# mpc56_cpuio2.net
KiCad netlist of a schematic drawn in Altium Designer
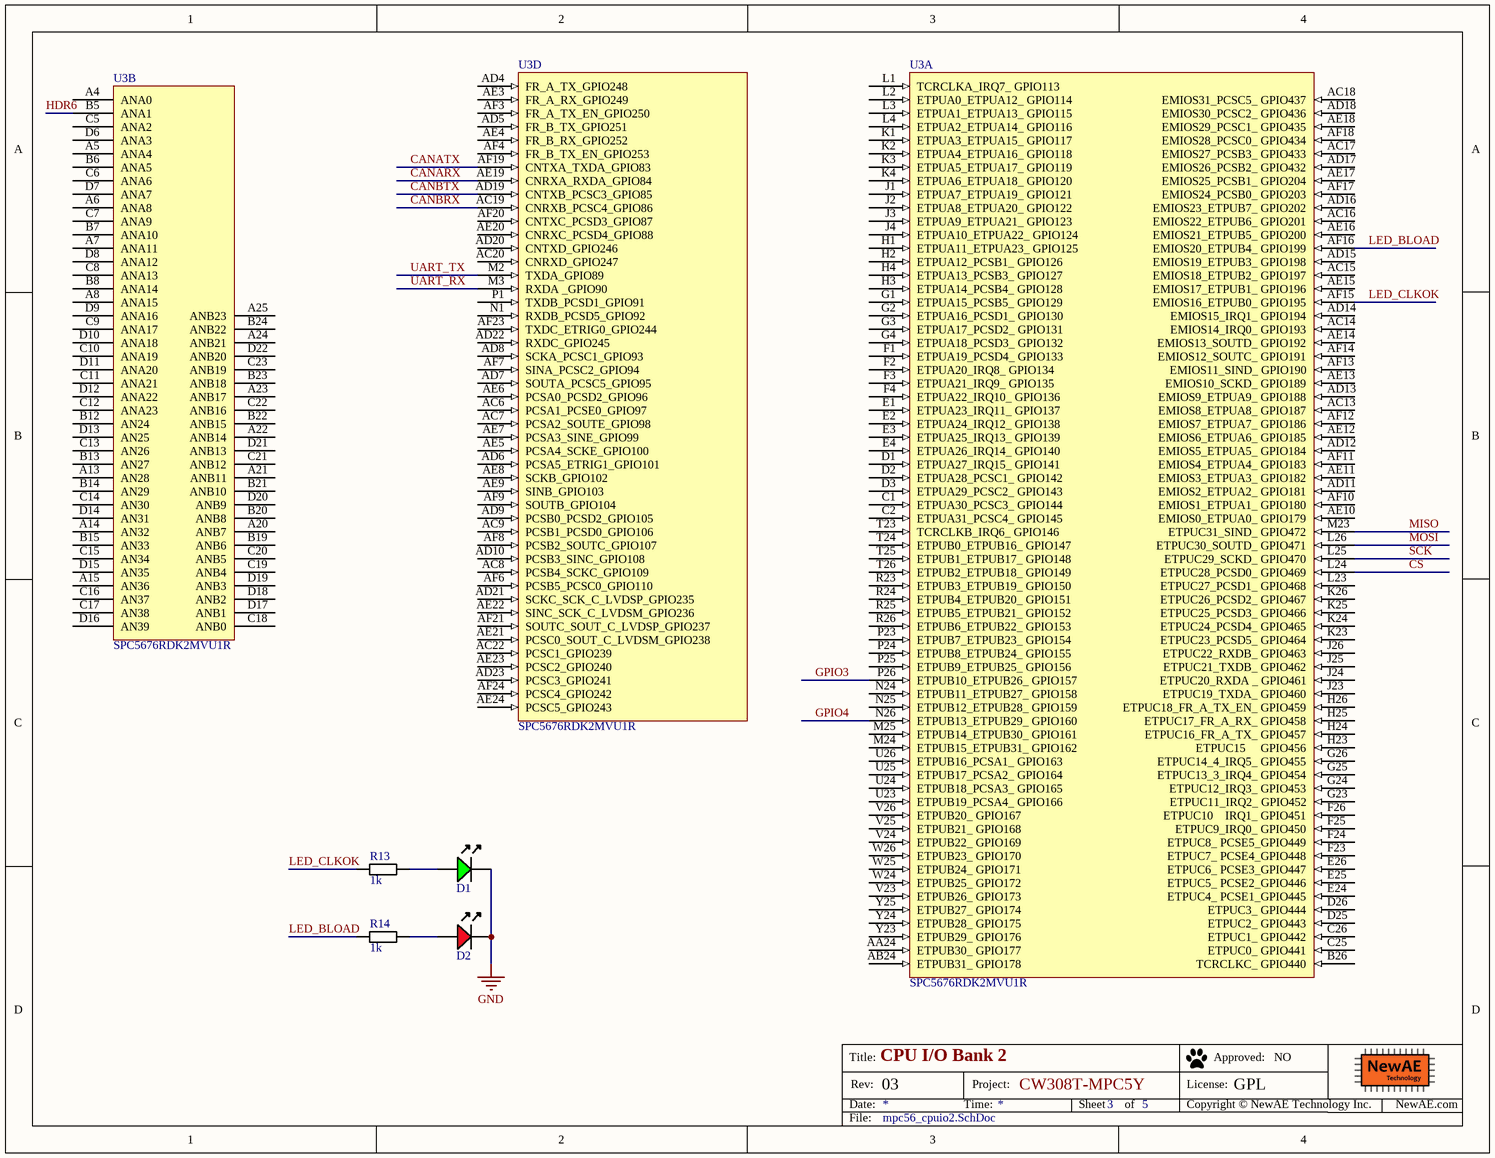
[diagram p0: mpc56_cpuio2.SchDoc]

(export (version "E")
  (design (tool "Eeschema 10.0.6"))
  (components
    (comp (ref "D1")
      (value "LED, 0603, Green")
      (footprint "LED-0603-GREEN")
      (description "Chip LED, Green")
      (fields (field (name "PART NUMBER") "LEDCHIP_0603_GREEN"))
      (libsource (lib "NewAE_AltiumLib") (part "LED_GREEN"))
    )
    (comp (ref "D2")
      (value "LED, 0603, Red")
      (footprint "LED-0603-RED")
      (description "Chip LED, Red")
      (fields (field (name "PART NUMBER") "LEDCHIP_0603_RED"))
      (libsource (lib "NewAE_AltiumLib") (part "LED_RED"))
    )
    (comp (ref "R13")
      (value "1k")
      (footprint "RESC1608X55N")
      (description "1k res, 0603, 1%, 1/10W")
      (fields (field (name "PART NUMBER") "RCHIP-1K-0603") (field (name "TOLERANCE") "1%"))
      (libsource (lib "NewAE_AltiumLib") (part "RES-EU"))
    )
    (comp (ref "R14")
      (value "1k")
      (footprint "RESC1608X55N")
      (description "1k res, 0603, 1%, 1/10W")
      (fields (field (name "PART NUMBER") "RCHIP-1K-0603") (field (name "TOLERANCE") "1%"))
      (libsource (lib "NewAE_AltiumLib") (part "RES-EU"))
    )
    (comp (ref "U3")
      (value "SPC5676RDK2MVU1R")
      (footprint "TEPBGA416_27x27")
      (description "Dual-Core PPC, Automotive")
      (libsource (lib "NewAE_AltiumLib") (part "SPC5676RDK2MVU1R"))
    )
  )
  (nets
    (net (code "1") (name "/CANARX") (class "Default")
      (node (ref "U3") (pin "AE19") (pinfunction "CNRXA_RXDA_GPIO84_AE19") (pintype "input"))
    )
    (net (code "2") (name "/CANATX") (class "Default")
      (node (ref "U3") (pin "AF19") (pinfunction "CNTXA_TXDA_GPIO83_AF19") (pintype "input"))
    )
    (net (code "3") (name "/CANBRX") (class "Default")
      (node (ref "U3") (pin "AC19") (pinfunction "CNRXB_PCSC4_GPIO86_AC19") (pintype "input"))
    )
    (net (code "4") (name "/CANBTX") (class "Default")
      (node (ref "U3") (pin "AD19") (pinfunction "CNTXB_PCSC3_GPIO85_AD19") (pintype "input"))
    )
    (net (code "5") (name "/CS") (class "Default")
      (node (ref "U3") (pin "L24") (pinfunction "ETPUC28_PCSD0__GPIO469_L24") (pintype "input"))
    )
    (net (code "6") (name "/GPIO3") (class "Default")
      (node (ref "U3") (pin "P26") (pinfunction "ETPUB10_ETPUB26__GPIO157_P26") (pintype "input"))
    )
    (net (code "7") (name "/GPIO4") (class "Default")
      (node (ref "U3") (pin "N26") (pinfunction "ETPUB13_ETPUB29__GPIO160_N26") (pintype "input"))
    )
    (net (code "8") (name "/HDR6") (class "Default")
      (node (ref "U3") (pin "B5") (pinfunction "ANA1_B5") (pintype "passive"))
    )
    (net (code "9") (name "/LED_BLOAD") (class "Default")
      (node (ref "R14") (pin "1") (pinfunction "1_1") (pintype "passive"))
      (node (ref "U3") (pin "AF16") (pinfunction "EMIOS20_ETPUB4__GPIO199_AF16") (pintype "input"))
    )
    (net (code "10") (name "/LED_CLKOK") (class "Default")
      (node (ref "R13") (pin "1") (pinfunction "1_1") (pintype "passive"))
      (node (ref "U3") (pin "AF15") (pinfunction "EMIOS16_ETPUB0__GPIO195_AF15") (pintype "input"))
    )
    (net (code "11") (name "/MISO") (class "Default")
      (node (ref "U3") (pin "M23") (pinfunction "ETPUC31_SIND__GPIO472_M23") (pintype "input"))
    )
    (net (code "12") (name "/MOSI") (class "Default")
      (node (ref "U3") (pin "L26") (pinfunction "ETPUC30_SOUTD__GPIO471_L26") (pintype "input"))
    )
    (net (code "13") (name "/SCK") (class "Default")
      (node (ref "U3") (pin "L25") (pinfunction "ETPUC29_SCKD__GPIO470_L25") (pintype "input"))
    )
    (net (code "14") (name "/UART_RX") (class "Default")
      (node (ref "U3") (pin "M3") (pinfunction "RXDA__GPIO90_M3") (pintype "input"))
    )
    (net (code "15") (name "/UART_TX") (class "Default")
      (node (ref "U3") (pin "M2") (pinfunction "TXDA_GPIO89_M2") (pintype "input"))
    )
    (net (code "16") (name "GND") (class "Default")
      (node (ref "D1") (pin "K") (pinfunction "K_K") (pintype "passive"))
      (node (ref "D2") (pin "K") (pinfunction "K_K") (pintype "passive"))
    )
    (net (code "17") (name "Net-(D1-PadA)") (class "Default")
      (node (ref "D1") (pin "A") (pinfunction "A_A") (pintype "passive"))
      (node (ref "R13") (pin "2") (pinfunction "2_2") (pintype "passive"))
    )
    (net (code "18") (name "Net-(D2-PadA)") (class "Default")
      (node (ref "D2") (pin "A") (pinfunction "A_A") (pintype "passive"))
      (node (ref "R14") (pin "2") (pinfunction "2_2") (pintype "passive"))
    )
    (net (code "19") (name "unconnected-(U3A-EMIOS0_ETPUA0__GPIO179-PadAE10)") (class "Default")
      (node (ref "U3") (pin "AE10") (pinfunction "EMIOS0_ETPUA0__GPIO179_AE10") (pintype "input"))
    )
    (net (code "20") (name "unconnected-(U3A-EMIOS1_ETPUA1__GPIO180-PadAF10)") (class "Default")
      (node (ref "U3") (pin "AF10") (pinfunction "EMIOS1_ETPUA1__GPIO180_AF10") (pintype "input"))
    )
    (net (code "21") (name "unconnected-(U3A-EMIOS2_ETPUA2__GPIO181-PadAD11)") (class "Default")
      (node (ref "U3") (pin "AD11") (pinfunction "EMIOS2_ETPUA2__GPIO181_AD11") (pintype "input"))
    )
    (net (code "22") (name "unconnected-(U3A-EMIOS3_ETPUA3__GPIO182-PadAE11)") (class "Default")
      (node (ref "U3") (pin "AE11") (pinfunction "EMIOS3_ETPUA3__GPIO182_AE11") (pintype "input"))
    )
    (net (code "23") (name "unconnected-(U3A-EMIOS4_ETPUA4__GPIO183-PadAF11)") (class "Default")
      (node (ref "U3") (pin "AF11") (pinfunction "EMIOS4_ETPUA4__GPIO183_AF11") (pintype "input"))
    )
    (net (code "24") (name "unconnected-(U3A-EMIOS5_ETPUA5__GPIO184-PadAD12)") (class "Default")
      (node (ref "U3") (pin "AD12") (pinfunction "EMIOS5_ETPUA5__GPIO184_AD12") (pintype "input"))
    )
    (net (code "25") (name "unconnected-(U3A-EMIOS6_ETPUA6__GPIO185-PadAE12)") (class "Default")
      (node (ref "U3") (pin "AE12") (pinfunction "EMIOS6_ETPUA6__GPIO185_AE12") (pintype "input"))
    )
    (net (code "26") (name "unconnected-(U3A-EMIOS7_ETPUA7__GPIO186-PadAF12)") (class "Default")
      (node (ref "U3") (pin "AF12") (pinfunction "EMIOS7_ETPUA7__GPIO186_AF12") (pintype "input"))
    )
    (net (code "27") (name "unconnected-(U3A-EMIOS8_ETPUA8__GPIO187-PadAC13)") (class "Default")
      (node (ref "U3") (pin "AC13") (pinfunction "EMIOS8_ETPUA8__GPIO187_AC13") (pintype "input"))
    )
    (net (code "28") (name "unconnected-(U3A-EMIOS9_ETPUA9__GPIO188-PadAD13)") (class "Default")
      (node (ref "U3") (pin "AD13") (pinfunction "EMIOS9_ETPUA9__GPIO188_AD13") (pintype "input"))
    )
    (net (code "29") (name "unconnected-(U3A-EMIOS10_SCKD__GPIO189-PadAE13)") (class "Default")
      (node (ref "U3") (pin "AE13") (pinfunction "EMIOS10_SCKD__GPIO189_AE13") (pintype "input"))
    )
    (net (code "30") (name "unconnected-(U3A-EMIOS11_SIND__GPIO190-PadAF13)") (class "Default")
      (node (ref "U3") (pin "AF13") (pinfunction "EMIOS11_SIND__GPIO190_AF13") (pintype "input"))
    )
    (net (code "31") (name "unconnected-(U3A-EMIOS12_SOUTC__GPIO191-PadAF14)") (class "Default")
      (node (ref "U3") (pin "AF14") (pinfunction "EMIOS12_SOUTC__GPIO191_AF14") (pintype "input"))
    )
    (net (code "32") (name "unconnected-(U3A-EMIOS13_SOUTD__GPIO192-PadAE14)") (class "Default")
      (node (ref "U3") (pin "AE14") (pinfunction "EMIOS13_SOUTD__GPIO192_AE14") (pintype "input"))
    )
    (net (code "33") (name "unconnected-(U3A-EMIOS14_IRQ0__GPIO193-PadAC14)") (class "Default")
      (node (ref "U3") (pin "AC14") (pinfunction "EMIOS14_IRQ0__GPIO193_AC14") (pintype "input"))
    )
    (net (code "34") (name "unconnected-(U3A-EMIOS15_IRQ1__GPIO194-PadAD14)") (class "Default")
      (node (ref "U3") (pin "AD14") (pinfunction "EMIOS15_IRQ1__GPIO194_AD14") (pintype "input"))
    )
    (net (code "35") (name "unconnected-(U3A-EMIOS17_ETPUB1__GPIO196-PadAE15)") (class "Default")
      (node (ref "U3") (pin "AE15") (pinfunction "EMIOS17_ETPUB1__GPIO196_AE15") (pintype "input"))
    )
    (net (code "36") (name "unconnected-(U3A-EMIOS18_ETPUB2__GPIO197-PadAC15)") (class "Default")
      (node (ref "U3") (pin "AC15") (pinfunction "EMIOS18_ETPUB2__GPIO197_AC15") (pintype "input"))
    )
    (net (code "37") (name "unconnected-(U3A-EMIOS19_ETPUB3__GPIO198-PadAD15)") (class "Default")
      (node (ref "U3") (pin "AD15") (pinfunction "EMIOS19_ETPUB3__GPIO198_AD15") (pintype "input"))
    )
    (net (code "38") (name "unconnected-(U3A-EMIOS21_ETPUB5__GPIO200-PadAE16)") (class "Default")
      (node (ref "U3") (pin "AE16") (pinfunction "EMIOS21_ETPUB5__GPIO200_AE16") (pintype "input"))
    )
    (net (code "39") (name "unconnected-(U3A-EMIOS22_ETPUB6__GPIO201-PadAC16)") (class "Default")
      (node (ref "U3") (pin "AC16") (pinfunction "EMIOS22_ETPUB6__GPIO201_AC16") (pintype "input"))
    )
    (net (code "40") (name "unconnected-(U3A-EMIOS23_ETPUB7__GPIO202-PadAD16)") (class "Default")
      (node (ref "U3") (pin "AD16") (pinfunction "EMIOS23_ETPUB7__GPIO202_AD16") (pintype "input"))
    )
    (net (code "41") (name "unconnected-(U3A-EMIOS24_PCSB0__GPIO203-PadAF17)") (class "Default")
      (node (ref "U3") (pin "AF17") (pinfunction "EMIOS24_PCSB0__GPIO203_AF17") (pintype "input"))
    )
    (net (code "42") (name "unconnected-(U3A-EMIOS25_PCSB1__GPIO204-PadAE17)") (class "Default")
      (node (ref "U3") (pin "AE17") (pinfunction "EMIOS25_PCSB1__GPIO204_AE17") (pintype "input"))
    )
    (net (code "43") (name "unconnected-(U3A-EMIOS26_PCSB2__GPIO432-PadAD17)") (class "Default")
      (node (ref "U3") (pin "AD17") (pinfunction "EMIOS26_PCSB2__GPIO432_AD17") (pintype "input"))
    )
    (net (code "44") (name "unconnected-(U3A-EMIOS27_PCSB3__GPIO433-PadAC17)") (class "Default")
      (node (ref "U3") (pin "AC17") (pinfunction "EMIOS27_PCSB3__GPIO433_AC17") (pintype "input"))
    )
    (net (code "45") (name "unconnected-(U3A-EMIOS28_PCSC0__GPIO434-PadAF18)") (class "Default")
      (node (ref "U3") (pin "AF18") (pinfunction "EMIOS28_PCSC0__GPIO434_AF18") (pintype "input"))
    )
    (net (code "46") (name "unconnected-(U3A-EMIOS29_PCSC1__GPIO435-PadAE18)") (class "Default")
      (node (ref "U3") (pin "AE18") (pinfunction "EMIOS29_PCSC1__GPIO435_AE18") (pintype "input"))
    )
    (net (code "47") (name "unconnected-(U3A-EMIOS30_PCSC2__GPIO436-PadAD18)") (class "Default")
      (node (ref "U3") (pin "AD18") (pinfunction "EMIOS30_PCSC2__GPIO436_AD18") (pintype "input"))
    )
    (net (code "48") (name "unconnected-(U3A-EMIOS31_PCSC5__GPIO437-PadAC18)") (class "Default")
      (node (ref "U3") (pin "AC18") (pinfunction "EMIOS31_PCSC5__GPIO437_AC18") (pintype "input"))
    )
    (net (code "49") (name "unconnected-(U3A-ETPUA0_ETPUA12__GPIO114-PadL2)") (class "Default")
      (node (ref "U3") (pin "L2") (pinfunction "ETPUA0_ETPUA12__GPIO114_L2") (pintype "input"))
    )
    (net (code "50") (name "unconnected-(U3A-ETPUA1_ETPUA13__GPIO115-PadL3)") (class "Default")
      (node (ref "U3") (pin "L3") (pinfunction "ETPUA1_ETPUA13__GPIO115_L3") (pintype "input"))
    )
    (net (code "51") (name "unconnected-(U3A-ETPUA2_ETPUA14__GPIO116-PadL4)") (class "Default")
      (node (ref "U3") (pin "L4") (pinfunction "ETPUA2_ETPUA14__GPIO116_L4") (pintype "input"))
    )
    (net (code "52") (name "unconnected-(U3A-ETPUA3_ETPUA15__GPIO117-PadK1)") (class "Default")
      (node (ref "U3") (pin "K1") (pinfunction "ETPUA3_ETPUA15__GPIO117_K1") (pintype "input"))
    )
    (net (code "53") (name "unconnected-(U3A-ETPUA4_ETPUA16__GPIO118-PadK2)") (class "Default")
      (node (ref "U3") (pin "K2") (pinfunction "ETPUA4_ETPUA16__GPIO118_K2") (pintype "input"))
    )
    (net (code "54") (name "unconnected-(U3A-ETPUA5_ETPUA17__GPIO119-PadK3)") (class "Default")
      (node (ref "U3") (pin "K3") (pinfunction "ETPUA5_ETPUA17__GPIO119_K3") (pintype "input"))
    )
    (net (code "55") (name "unconnected-(U3A-ETPUA6_ETPUA18__GPIO120-PadK4)") (class "Default")
      (node (ref "U3") (pin "K4") (pinfunction "ETPUA6_ETPUA18__GPIO120_K4") (pintype "input"))
    )
    (net (code "56") (name "unconnected-(U3A-ETPUA7_ETPUA19__GPIO121-PadJ1)") (class "Default")
      (node (ref "U3") (pin "J1") (pinfunction "ETPUA7_ETPUA19__GPIO121_J1") (pintype "input"))
    )
    (net (code "57") (name "unconnected-(U3A-ETPUA8_ETPUA20__GPIO122-PadJ2)") (class "Default")
      (node (ref "U3") (pin "J2") (pinfunction "ETPUA8_ETPUA20__GPIO122_J2") (pintype "input"))
    )
    (net (code "58") (name "unconnected-(U3A-ETPUA9_ETPUA21__GPIO123-PadJ3)") (class "Default")
      (node (ref "U3") (pin "J3") (pinfunction "ETPUA9_ETPUA21__GPIO123_J3") (pintype "input"))
    )
    (net (code "59") (name "unconnected-(U3A-ETPUA10_ETPUA22__GPIO124-PadJ4)") (class "Default")
      (node (ref "U3") (pin "J4") (pinfunction "ETPUA10_ETPUA22__GPIO124_J4") (pintype "input"))
    )
    (net (code "60") (name "unconnected-(U3A-ETPUA11_ETPUA23__GPIO125-PadH1)") (class "Default")
      (node (ref "U3") (pin "H1") (pinfunction "ETPUA11_ETPUA23__GPIO125_H1") (pintype "input"))
    )
    (net (code "61") (name "unconnected-(U3A-ETPUA12_PCSB1__GPIO126-PadH2)") (class "Default")
      (node (ref "U3") (pin "H2") (pinfunction "ETPUA12_PCSB1__GPIO126_H2") (pintype "input"))
    )
    (net (code "62") (name "unconnected-(U3A-ETPUA13_PCSB3__GPIO127-PadH4)") (class "Default")
      (node (ref "U3") (pin "H4") (pinfunction "ETPUA13_PCSB3__GPIO127_H4") (pintype "input"))
    )
    (net (code "63") (name "unconnected-(U3A-ETPUA14_PCSB4__GPIO128-PadH3)") (class "Default")
      (node (ref "U3") (pin "H3") (pinfunction "ETPUA14_PCSB4__GPIO128_H3") (pintype "input"))
    )
    (net (code "64") (name "unconnected-(U3A-ETPUA15_PCSB5__GPIO129-PadG1)") (class "Default")
      (node (ref "U3") (pin "G1") (pinfunction "ETPUA15_PCSB5__GPIO129_G1") (pintype "input"))
    )
    (net (code "65") (name "unconnected-(U3A-ETPUA16_PCSD1__GPIO130-PadG2)") (class "Default")
      (node (ref "U3") (pin "G2") (pinfunction "ETPUA16_PCSD1__GPIO130_G2") (pintype "input"))
    )
    (net (code "66") (name "unconnected-(U3A-ETPUA17_PCSD2__GPIO131-PadG3)") (class "Default")
      (node (ref "U3") (pin "G3") (pinfunction "ETPUA17_PCSD2__GPIO131_G3") (pintype "input"))
    )
    (net (code "67") (name "unconnected-(U3A-ETPUA18_PCSD3__GPIO132-PadG4)") (class "Default")
      (node (ref "U3") (pin "G4") (pinfunction "ETPUA18_PCSD3__GPIO132_G4") (pintype "input"))
    )
    (net (code "68") (name "unconnected-(U3A-ETPUA19_PCSD4__GPIO133-PadF1)") (class "Default")
      (node (ref "U3") (pin "F1") (pinfunction "ETPUA19_PCSD4__GPIO133_F1") (pintype "input"))
    )
    (net (code "69") (name "unconnected-(U3A-ETPUA20_IRQ8__GPIO134-PadF2)") (class "Default")
      (node (ref "U3") (pin "F2") (pinfunction "ETPUA20_IRQ8__GPIO134_F2") (pintype "input"))
    )
    (net (code "70") (name "unconnected-(U3A-ETPUA21_IRQ9__GPIO135-PadF3)") (class "Default")
      (node (ref "U3") (pin "F3") (pinfunction "ETPUA21_IRQ9__GPIO135_F3") (pintype "input"))
    )
    (net (code "71") (name "unconnected-(U3A-ETPUA22_IRQ10__GPIO136-PadF4)") (class "Default")
      (node (ref "U3") (pin "F4") (pinfunction "ETPUA22_IRQ10__GPIO136_F4") (pintype "input"))
    )
    (net (code "72") (name "unconnected-(U3A-ETPUA23_IRQ11__GPIO137-PadE1)") (class "Default")
      (node (ref "U3") (pin "E1") (pinfunction "ETPUA23_IRQ11__GPIO137_E1") (pintype "input"))
    )
    (net (code "73") (name "unconnected-(U3A-ETPUA24_IRQ12__GPIO138-PadE2)") (class "Default")
      (node (ref "U3") (pin "E2") (pinfunction "ETPUA24_IRQ12__GPIO138_E2") (pintype "input"))
    )
    (net (code "74") (name "unconnected-(U3A-ETPUA25_IRQ13__GPIO139-PadE3)") (class "Default")
      (node (ref "U3") (pin "E3") (pinfunction "ETPUA25_IRQ13__GPIO139_E3") (pintype "input"))
    )
    (net (code "75") (name "unconnected-(U3A-ETPUA26_IRQ14__GPIO140-PadE4)") (class "Default")
      (node (ref "U3") (pin "E4") (pinfunction "ETPUA26_IRQ14__GPIO140_E4") (pintype "input"))
    )
    (net (code "76") (name "unconnected-(U3A-ETPUA27_IRQ15__GPIO141-PadD1)") (class "Default")
      (node (ref "U3") (pin "D1") (pinfunction "ETPUA27_IRQ15__GPIO141_D1") (pintype "input"))
    )
    (net (code "77") (name "unconnected-(U3A-ETPUA28_PCSC1__GPIO142-PadD2)") (class "Default")
      (node (ref "U3") (pin "D2") (pinfunction "ETPUA28_PCSC1__GPIO142_D2") (pintype "input"))
    )
    (net (code "78") (name "unconnected-(U3A-ETPUA29_PCSC2__GPIO143-PadD3)") (class "Default")
      (node (ref "U3") (pin "D3") (pinfunction "ETPUA29_PCSC2__GPIO143_D3") (pintype "input"))
    )
    (net (code "79") (name "unconnected-(U3A-ETPUA30_PCSC3__GPIO144-PadC1)") (class "Default")
      (node (ref "U3") (pin "C1") (pinfunction "ETPUA30_PCSC3__GPIO144_C1") (pintype "input"))
    )
    (net (code "80") (name "unconnected-(U3A-ETPUA31_PCSC4__GPIO145-PadC2)") (class "Default")
      (node (ref "U3") (pin "C2") (pinfunction "ETPUA31_PCSC4__GPIO145_C2") (pintype "input"))
    )
    (net (code "81") (name "unconnected-(U3A-ETPUB0_ETPUB16__GPIO147-PadT24)") (class "Default")
      (node (ref "U3") (pin "T24") (pinfunction "ETPUB0_ETPUB16__GPIO147_T24") (pintype "input"))
    )
    (net (code "82") (name "unconnected-(U3A-ETPUB1_ETPUB17__GPIO148-PadT25)") (class "Default")
      (node (ref "U3") (pin "T25") (pinfunction "ETPUB1_ETPUB17__GPIO148_T25") (pintype "input"))
    )
    (net (code "83") (name "unconnected-(U3A-ETPUB2_ETPUB18__GPIO149-PadT26)") (class "Default")
      (node (ref "U3") (pin "T26") (pinfunction "ETPUB2_ETPUB18__GPIO149_T26") (pintype "input"))
    )
    (net (code "84") (name "unconnected-(U3A-ETPUB3_ETPUB19__GPIO150-PadR23)") (class "Default")
      (node (ref "U3") (pin "R23") (pinfunction "ETPUB3_ETPUB19__GPIO150_R23") (pintype "input"))
    )
    (net (code "85") (name "unconnected-(U3A-ETPUB4_ETPUB20__GPIO151-PadR24)") (class "Default")
      (node (ref "U3") (pin "R24") (pinfunction "ETPUB4_ETPUB20__GPIO151_R24") (pintype "input"))
    )
    (net (code "86") (name "unconnected-(U3A-ETPUB5_ETPUB21__GPIO152-PadR25)") (class "Default")
      (node (ref "U3") (pin "R25") (pinfunction "ETPUB5_ETPUB21__GPIO152_R25") (pintype "input"))
    )
    (net (code "87") (name "unconnected-(U3A-ETPUB6_ETPUB22__GPIO153-PadR26)") (class "Default")
      (node (ref "U3") (pin "R26") (pinfunction "ETPUB6_ETPUB22__GPIO153_R26") (pintype "input"))
    )
    (net (code "88") (name "unconnected-(U3A-ETPUB7_ETPUB23__GPIO154-PadP23)") (class "Default")
      (node (ref "U3") (pin "P23") (pinfunction "ETPUB7_ETPUB23__GPIO154_P23") (pintype "input"))
    )
    (net (code "89") (name "unconnected-(U3A-ETPUB8_ETPUB24__GPIO155-PadP24)") (class "Default")
      (node (ref "U3") (pin "P24") (pinfunction "ETPUB8_ETPUB24__GPIO155_P24") (pintype "input"))
    )
    (net (code "90") (name "unconnected-(U3A-ETPUB9_ETPUB25__GPIO156-PadP25)") (class "Default")
      (node (ref "U3") (pin "P25") (pinfunction "ETPUB9_ETPUB25__GPIO156_P25") (pintype "input"))
    )
    (net (code "91") (name "unconnected-(U3A-ETPUB11_ETPUB27__GPIO158-PadN24)") (class "Default")
      (node (ref "U3") (pin "N24") (pinfunction "ETPUB11_ETPUB27__GPIO158_N24") (pintype "input"))
    )
    (net (code "92") (name "unconnected-(U3A-ETPUB12_ETPUB28__GPIO159-PadN25)") (class "Default")
      (node (ref "U3") (pin "N25") (pinfunction "ETPUB12_ETPUB28__GPIO159_N25") (pintype "input"))
    )
    (net (code "93") (name "unconnected-(U3A-ETPUB14_ETPUB30__GPIO161-PadM25)") (class "Default")
      (node (ref "U3") (pin "M25") (pinfunction "ETPUB14_ETPUB30__GPIO161_M25") (pintype "input"))
    )
    (net (code "94") (name "unconnected-(U3A-ETPUB15_ETPUB31__GPIO162-PadM24)") (class "Default")
      (node (ref "U3") (pin "M24") (pinfunction "ETPUB15_ETPUB31__GPIO162_M24") (pintype "input"))
    )
    (net (code "95") (name "unconnected-(U3A-ETPUB16_PCSA1__GPIO163-PadU26)") (class "Default")
      (node (ref "U3") (pin "U26") (pinfunction "ETPUB16_PCSA1__GPIO163_U26") (pintype "input"))
    )
    (net (code "96") (name "unconnected-(U3A-ETPUB17_PCSA2__GPIO164-PadU25)") (class "Default")
      (node (ref "U3") (pin "U25") (pinfunction "ETPUB17_PCSA2__GPIO164_U25") (pintype "input"))
    )
    (net (code "97") (name "unconnected-(U3A-ETPUB18_PCSA3__GPIO165-PadU24)") (class "Default")
      (node (ref "U3") (pin "U24") (pinfunction "ETPUB18_PCSA3__GPIO165_U24") (pintype "input"))
    )
    (net (code "98") (name "unconnected-(U3A-ETPUB19_PCSA4__GPIO166-PadU23)") (class "Default")
      (node (ref "U3") (pin "U23") (pinfunction "ETPUB19_PCSA4__GPIO166_U23") (pintype "input"))
    )
    (net (code "99") (name "unconnected-(U3A-ETPUB20__GPIO167-PadV26)") (class "Default")
      (node (ref "U3") (pin "V26") (pinfunction "ETPUB20__GPIO167_V26") (pintype "input"))
    )
    (net (code "100") (name "unconnected-(U3A-ETPUB21__GPIO168-PadV25)") (class "Default")
      (node (ref "U3") (pin "V25") (pinfunction "ETPUB21__GPIO168_V25") (pintype "input"))
    )
    (net (code "101") (name "unconnected-(U3A-ETPUB22__GPIO169-PadV24)") (class "Default")
      (node (ref "U3") (pin "V24") (pinfunction "ETPUB22__GPIO169_V24") (pintype "input"))
    )
    (net (code "102") (name "unconnected-(U3A-ETPUB23__GPIO170-PadW26)") (class "Default")
      (node (ref "U3") (pin "W26") (pinfunction "ETPUB23__GPIO170_W26") (pintype "input"))
    )
    (net (code "103") (name "unconnected-(U3A-ETPUB24__GPIO171-PadW25)") (class "Default")
      (node (ref "U3") (pin "W25") (pinfunction "ETPUB24__GPIO171_W25") (pintype "input"))
    )
    (net (code "104") (name "unconnected-(U3A-ETPUB25__GPIO172-PadW24)") (class "Default")
      (node (ref "U3") (pin "W24") (pinfunction "ETPUB25__GPIO172_W24") (pintype "input"))
    )
    (net (code "105") (name "unconnected-(U3A-ETPUB26__GPIO173-PadV23)") (class "Default")
      (node (ref "U3") (pin "V23") (pinfunction "ETPUB26__GPIO173_V23") (pintype "input"))
    )
    (net (code "106") (name "unconnected-(U3A-ETPUB27__GPIO174-PadY25)") (class "Default")
      (node (ref "U3") (pin "Y25") (pinfunction "ETPUB27__GPIO174_Y25") (pintype "input"))
    )
    (net (code "107") (name "unconnected-(U3A-ETPUB28__GPIO175-PadY24)") (class "Default")
      (node (ref "U3") (pin "Y24") (pinfunction "ETPUB28__GPIO175_Y24") (pintype "input"))
    )
    (net (code "108") (name "unconnected-(U3A-ETPUB29__GPIO176-PadY23)") (class "Default")
      (node (ref "U3") (pin "Y23") (pinfunction "ETPUB29__GPIO176_Y23") (pintype "input"))
    )
    (net (code "109") (name "unconnected-(U3A-ETPUB30__GPIO177-PadAA24)") (class "Default")
      (node (ref "U3") (pin "AA24") (pinfunction "ETPUB30__GPIO177_AA24") (pintype "input"))
    )
    (net (code "110") (name "unconnected-(U3A-ETPUB31__GPIO178-PadAB24)") (class "Default")
      (node (ref "U3") (pin "AB24") (pinfunction "ETPUB31__GPIO178_AB24") (pintype "input"))
    )
    (net (code "111") (name "unconnected-(U3A-ETPUC0__GPIO441-PadC25)") (class "Default")
      (node (ref "U3") (pin "C25") (pinfunction "ETPUC0__GPIO441_C25") (pintype "input"))
    )
    (net (code "112") (name "unconnected-(U3A-ETPUC1__GPIO442-PadC26)") (class "Default")
      (node (ref "U3") (pin "C26") (pinfunction "ETPUC1__GPIO442_C26") (pintype "input"))
    )
    (net (code "113") (name "unconnected-(U3A-ETPUC2__GPIO443-PadD25)") (class "Default")
      (node (ref "U3") (pin "D25") (pinfunction "ETPUC2__GPIO443_D25") (pintype "input"))
    )
    (net (code "114") (name "unconnected-(U3A-ETPUC3__GPIO444-PadD26)") (class "Default")
      (node (ref "U3") (pin "D26") (pinfunction "ETPUC3__GPIO444_D26") (pintype "input"))
    )
    (net (code "115") (name "unconnected-(U3A-ETPUC4__PCSE1_GPIO445-PadE24)") (class "Default")
      (node (ref "U3") (pin "E24") (pinfunction "ETPUC4__PCSE1_GPIO445_E24") (pintype "input"))
    )
    (net (code "116") (name "unconnected-(U3A-ETPUC5__PCSE2_GPIO446-PadE25)") (class "Default")
      (node (ref "U3") (pin "E25") (pinfunction "ETPUC5__PCSE2_GPIO446_E25") (pintype "input"))
    )
    (net (code "117") (name "unconnected-(U3A-ETPUC6__PCSE3_GPIO447-PadE26)") (class "Default")
      (node (ref "U3") (pin "E26") (pinfunction "ETPUC6__PCSE3_GPIO447_E26") (pintype "input"))
    )
    (net (code "118") (name "unconnected-(U3A-ETPUC7__PCSE4_GPIO448-PadF23)") (class "Default")
      (node (ref "U3") (pin "F23") (pinfunction "ETPUC7__PCSE4_GPIO448_F23") (pintype "input"))
    )
    (net (code "119") (name "unconnected-(U3A-ETPUC8__PCSE5_GPIO449-PadF24)") (class "Default")
      (node (ref "U3") (pin "F24") (pinfunction "ETPUC8__PCSE5_GPIO449_F24") (pintype "input"))
    )
    (net (code "120") (name "unconnected-(U3A-ETPUC9_IRQ0__GPIO450-PadF25)") (class "Default")
      (node (ref "U3") (pin "F25") (pinfunction "ETPUC9_IRQ0__GPIO450_F25") (pintype "input"))
    )
    (net (code "121") (name "unconnected-(U3A-ETPUC10    IRQ1__GPIO451-PadF26)") (class "Default")
      (node (ref "U3") (pin "F26") (pinfunction "ETPUC10    IRQ1__GPIO451_F26") (pintype "input"))
    )
    (net (code "122") (name "unconnected-(U3A-ETPUC11_IRQ2__GPIO452-PadG23)") (class "Default")
      (node (ref "U3") (pin "G23") (pinfunction "ETPUC11_IRQ2__GPIO452_G23") (pintype "input"))
    )
    (net (code "123") (name "unconnected-(U3A-ETPUC12_IRQ3__GPIO453-PadG24)") (class "Default")
      (node (ref "U3") (pin "G24") (pinfunction "ETPUC12_IRQ3__GPIO453_G24") (pintype "input"))
    )
    (net (code "124") (name "unconnected-(U3A-ETPUC13_3_IRQ4__GPIO454-PadG25)") (class "Default")
      (node (ref "U3") (pin "G25") (pinfunction "ETPUC13_3_IRQ4__GPIO454_G25") (pintype "input"))
    )
    (net (code "125") (name "unconnected-(U3A-ETPUC14_4_IRQ5__GPIO455-PadG26)") (class "Default")
      (node (ref "U3") (pin "G26") (pinfunction "ETPUC14_4_IRQ5__GPIO455_G26") (pintype "input"))
    )
    (net (code "126") (name "unconnected-(U3A-ETPUC15    _GPIO456-PadH23)") (class "Default")
      (node (ref "U3") (pin "H23") (pinfunction "ETPUC15    _GPIO456_H23") (pintype "input"))
    )
    (net (code "127") (name "unconnected-(U3A-ETPUC16_FR_A_TX__GPIO457-PadH24)") (class "Default")
      (node (ref "U3") (pin "H24") (pinfunction "ETPUC16_FR_A_TX__GPIO457_H24") (pintype "input"))
    )
    (net (code "128") (name "unconnected-(U3A-ETPUC17_FR_A_RX__GPIO458-PadH25)") (class "Default")
      (node (ref "U3") (pin "H25") (pinfunction "ETPUC17_FR_A_RX__GPIO458_H25") (pintype "input"))
    )
    (net (code "129") (name "unconnected-(U3A-ETPUC18_FR_A_TX_EN__GPIO459-PadH26)") (class "Default")
      (node (ref "U3") (pin "H26") (pinfunction "ETPUC18_FR_A_TX_EN__GPIO459_H26") (pintype "input"))
    )
    (net (code "130") (name "unconnected-(U3A-ETPUC19_TXDA__GPIO460-PadJ23)") (class "Default")
      (node (ref "U3") (pin "J23") (pinfunction "ETPUC19_TXDA__GPIO460_J23") (pintype "input"))
    )
    (net (code "131") (name "unconnected-(U3A-ETPUC20_RXDA___GPIO461-PadJ24)") (class "Default")
      (node (ref "U3") (pin "J24") (pinfunction "ETPUC20_RXDA___GPIO461_J24") (pintype "input"))
    )
    (net (code "132") (name "unconnected-(U3A-ETPUC21_TXDB__GPIO462-PadJ25)") (class "Default")
      (node (ref "U3") (pin "J25") (pinfunction "ETPUC21_TXDB__GPIO462_J25") (pintype "input"))
    )
    (net (code "133") (name "unconnected-(U3A-ETPUC22_RXDB__GPIO463-PadJ26)") (class "Default")
      (node (ref "U3") (pin "J26") (pinfunction "ETPUC22_RXDB__GPIO463_J26") (pintype "input"))
    )
    (net (code "134") (name "unconnected-(U3A-ETPUC23_PCSD5__GPIO464-PadK23)") (class "Default")
      (node (ref "U3") (pin "K23") (pinfunction "ETPUC23_PCSD5__GPIO464_K23") (pintype "input"))
    )
    (net (code "135") (name "unconnected-(U3A-ETPUC24_PCSD4__GPIO465-PadK24)") (class "Default")
      (node (ref "U3") (pin "K24") (pinfunction "ETPUC24_PCSD4__GPIO465_K24") (pintype "input"))
    )
    (net (code "136") (name "unconnected-(U3A-ETPUC25_PCSD3__GPIO466-PadK25)") (class "Default")
      (node (ref "U3") (pin "K25") (pinfunction "ETPUC25_PCSD3__GPIO466_K25") (pintype "input"))
    )
    (net (code "137") (name "unconnected-(U3A-ETPUC26_PCSD2__GPIO467-PadK26)") (class "Default")
      (node (ref "U3") (pin "K26") (pinfunction "ETPUC26_PCSD2__GPIO467_K26") (pintype "input"))
    )
    (net (code "138") (name "unconnected-(U3A-ETPUC27_PCSD1__GPIO468-PadL23)") (class "Default")
      (node (ref "U3") (pin "L23") (pinfunction "ETPUC27_PCSD1__GPIO468_L23") (pintype "input"))
    )
    (net (code "139") (name "unconnected-(U3A-TCRCLKA_IRQ7__GPIO113-PadL1)") (class "Default")
      (node (ref "U3") (pin "L1") (pinfunction "TCRCLKA_IRQ7__GPIO113_L1") (pintype "input"))
    )
    (net (code "140") (name "unconnected-(U3A-TCRCLKB_IRQ6__GPIO146-PadT23)") (class "Default")
      (node (ref "U3") (pin "T23") (pinfunction "TCRCLKB_IRQ6__GPIO146_T23") (pintype "input"))
    )
    (net (code "141") (name "unconnected-(U3A-TCRCLKC__GPIO440-PadB26)") (class "Default")
      (node (ref "U3") (pin "B26") (pinfunction "TCRCLKC__GPIO440_B26") (pintype "input"))
    )
    (net (code "142") (name "unconnected-(U3B-AN24-PadB12)") (class "Default")
      (node (ref "U3") (pin "B12") (pinfunction "AN24_B12") (pintype "passive"))
    )
    (net (code "143") (name "unconnected-(U3B-AN25-PadD13)") (class "Default")
      (node (ref "U3") (pin "D13") (pinfunction "AN25_D13") (pintype "passive"))
    )
    (net (code "144") (name "unconnected-(U3B-AN26-PadC13)") (class "Default")
      (node (ref "U3") (pin "C13") (pinfunction "AN26_C13") (pintype "passive"))
    )
    (net (code "145") (name "unconnected-(U3B-AN27-PadB13)") (class "Default")
      (node (ref "U3") (pin "B13") (pinfunction "AN27_B13") (pintype "passive"))
    )
    (net (code "146") (name "unconnected-(U3B-AN28-PadA13)") (class "Default")
      (node (ref "U3") (pin "A13") (pinfunction "AN28_A13") (pintype "passive"))
    )
    (net (code "147") (name "unconnected-(U3B-AN29-PadB14)") (class "Default")
      (node (ref "U3") (pin "B14") (pinfunction "AN29_B14") (pintype "passive"))
    )
    (net (code "148") (name "unconnected-(U3B-AN30-PadC14)") (class "Default")
      (node (ref "U3") (pin "C14") (pinfunction "AN30_C14") (pintype "passive"))
    )
    (net (code "149") (name "unconnected-(U3B-AN31-PadD14)") (class "Default")
      (node (ref "U3") (pin "D14") (pinfunction "AN31_D14") (pintype "passive"))
    )
    (net (code "150") (name "unconnected-(U3B-AN32-PadA14)") (class "Default")
      (node (ref "U3") (pin "A14") (pinfunction "AN32_A14") (pintype "passive"))
    )
    (net (code "151") (name "unconnected-(U3B-AN33-PadB15)") (class "Default")
      (node (ref "U3") (pin "B15") (pinfunction "AN33_B15") (pintype "passive"))
    )
    (net (code "152") (name "unconnected-(U3B-AN34-PadC15)") (class "Default")
      (node (ref "U3") (pin "C15") (pinfunction "AN34_C15") (pintype "passive"))
    )
    (net (code "153") (name "unconnected-(U3B-AN35-PadD15)") (class "Default")
      (node (ref "U3") (pin "D15") (pinfunction "AN35_D15") (pintype "passive"))
    )
    (net (code "154") (name "unconnected-(U3B-AN36-PadA15)") (class "Default")
      (node (ref "U3") (pin "A15") (pinfunction "AN36_A15") (pintype "passive"))
    )
    (net (code "155") (name "unconnected-(U3B-AN37-PadC16)") (class "Default")
      (node (ref "U3") (pin "C16") (pinfunction "AN37_C16") (pintype "passive"))
    )
    (net (code "156") (name "unconnected-(U3B-AN38-PadC17)") (class "Default")
      (node (ref "U3") (pin "C17") (pinfunction "AN38_C17") (pintype "passive"))
    )
    (net (code "157") (name "unconnected-(U3B-AN39-PadD16)") (class "Default")
      (node (ref "U3") (pin "D16") (pinfunction "AN39_D16") (pintype "passive"))
    )
    (net (code "158") (name "unconnected-(U3B-ANA0-PadA4)") (class "Default")
      (node (ref "U3") (pin "A4") (pinfunction "ANA0_A4") (pintype "passive"))
    )
    (net (code "159") (name "unconnected-(U3B-ANA2-PadC5)") (class "Default")
      (node (ref "U3") (pin "C5") (pinfunction "ANA2_C5") (pintype "passive"))
    )
    (net (code "160") (name "unconnected-(U3B-ANA3-PadD6)") (class "Default")
      (node (ref "U3") (pin "D6") (pinfunction "ANA3_D6") (pintype "passive"))
    )
    (net (code "161") (name "unconnected-(U3B-ANA4-PadA5)") (class "Default")
      (node (ref "U3") (pin "A5") (pinfunction "ANA4_A5") (pintype "passive"))
    )
    (net (code "162") (name "unconnected-(U3B-ANA5-PadB6)") (class "Default")
      (node (ref "U3") (pin "B6") (pinfunction "ANA5_B6") (pintype "passive"))
    )
    (net (code "163") (name "unconnected-(U3B-ANA6-PadC6)") (class "Default")
      (node (ref "U3") (pin "C6") (pinfunction "ANA6_C6") (pintype "passive"))
    )
    (net (code "164") (name "unconnected-(U3B-ANA7-PadD7)") (class "Default")
      (node (ref "U3") (pin "D7") (pinfunction "ANA7_D7") (pintype "passive"))
    )
    (net (code "165") (name "unconnected-(U3B-ANA8-PadA6)") (class "Default")
      (node (ref "U3") (pin "A6") (pinfunction "ANA8_A6") (pintype "passive"))
    )
    (net (code "166") (name "unconnected-(U3B-ANA9-PadC7)") (class "Default")
      (node (ref "U3") (pin "C7") (pinfunction "ANA9_C7") (pintype "passive"))
    )
    (net (code "167") (name "unconnected-(U3B-ANA10-PadB7)") (class "Default")
      (node (ref "U3") (pin "B7") (pinfunction "ANA10_B7") (pintype "passive"))
    )
    (net (code "168") (name "unconnected-(U3B-ANA11-PadA7)") (class "Default")
      (node (ref "U3") (pin "A7") (pinfunction "ANA11_A7") (pintype "passive"))
    )
    (net (code "169") (name "unconnected-(U3B-ANA12-PadD8)") (class "Default")
      (node (ref "U3") (pin "D8") (pinfunction "ANA12_D8") (pintype "passive"))
    )
    (net (code "170") (name "unconnected-(U3B-ANA13-PadC8)") (class "Default")
      (node (ref "U3") (pin "C8") (pinfunction "ANA13_C8") (pintype "passive"))
    )
    (net (code "171") (name "unconnected-(U3B-ANA14-PadB8)") (class "Default")
      (node (ref "U3") (pin "B8") (pinfunction "ANA14_B8") (pintype "passive"))
    )
    (net (code "172") (name "unconnected-(U3B-ANA15-PadA8)") (class "Default")
      (node (ref "U3") (pin "A8") (pinfunction "ANA15_A8") (pintype "passive"))
    )
    (net (code "173") (name "unconnected-(U3B-ANA16-PadD9)") (class "Default")
      (node (ref "U3") (pin "D9") (pinfunction "ANA16_D9") (pintype "passive"))
    )
    (net (code "174") (name "unconnected-(U3B-ANA17-PadC9)") (class "Default")
      (node (ref "U3") (pin "C9") (pinfunction "ANA17_C9") (pintype "passive"))
    )
    (net (code "175") (name "unconnected-(U3B-ANA18-PadD10)") (class "Default")
      (node (ref "U3") (pin "D10") (pinfunction "ANA18_D10") (pintype "passive"))
    )
    (net (code "176") (name "unconnected-(U3B-ANA19-PadC10)") (class "Default")
      (node (ref "U3") (pin "C10") (pinfunction "ANA19_C10") (pintype "passive"))
    )
    (net (code "177") (name "unconnected-(U3B-ANA20-PadD11)") (class "Default")
      (node (ref "U3") (pin "D11") (pinfunction "ANA20_D11") (pintype "passive"))
    )
    (net (code "178") (name "unconnected-(U3B-ANA21-PadC11)") (class "Default")
      (node (ref "U3") (pin "C11") (pinfunction "ANA21_C11") (pintype "passive"))
    )
    (net (code "179") (name "unconnected-(U3B-ANA22-PadD12)") (class "Default")
      (node (ref "U3") (pin "D12") (pinfunction "ANA22_D12") (pintype "passive"))
    )
    (net (code "180") (name "unconnected-(U3B-ANA23-PadC12)") (class "Default")
      (node (ref "U3") (pin "C12") (pinfunction "ANA23_C12") (pintype "passive"))
    )
    (net (code "181") (name "unconnected-(U3B-ANB0-PadC18)") (class "Default")
      (node (ref "U3") (pin "C18") (pinfunction "ANB0_C18") (pintype "passive"))
    )
    (net (code "182") (name "unconnected-(U3B-ANB1-PadD17)") (class "Default")
      (node (ref "U3") (pin "D17") (pinfunction "ANB1_D17") (pintype "passive"))
    )
    (net (code "183") (name "unconnected-(U3B-ANB2-PadD18)") (class "Default")
      (node (ref "U3") (pin "D18") (pinfunction "ANB2_D18") (pintype "passive"))
    )
    (net (code "184") (name "unconnected-(U3B-ANB3-PadD19)") (class "Default")
      (node (ref "U3") (pin "D19") (pinfunction "ANB3_D19") (pintype "passive"))
    )
    (net (code "185") (name "unconnected-(U3B-ANB4-PadC19)") (class "Default")
      (node (ref "U3") (pin "C19") (pinfunction "ANB4_C19") (pintype "passive"))
    )
    (net (code "186") (name "unconnected-(U3B-ANB5-PadC20)") (class "Default")
      (node (ref "U3") (pin "C20") (pinfunction "ANB5_C20") (pintype "passive"))
    )
    (net (code "187") (name "unconnected-(U3B-ANB6-PadB19)") (class "Default")
      (node (ref "U3") (pin "B19") (pinfunction "ANB6_B19") (pintype "passive"))
    )
    (net (code "188") (name "unconnected-(U3B-ANB7-PadA20)") (class "Default")
      (node (ref "U3") (pin "A20") (pinfunction "ANB7_A20") (pintype "passive"))
    )
    (net (code "189") (name "unconnected-(U3B-ANB8-PadB20)") (class "Default")
      (node (ref "U3") (pin "B20") (pinfunction "ANB8_B20") (pintype "passive"))
    )
    (net (code "190") (name "unconnected-(U3B-ANB9-PadD20)") (class "Default")
      (node (ref "U3") (pin "D20") (pinfunction "ANB9_D20") (pintype "passive"))
    )
    (net (code "191") (name "unconnected-(U3B-ANB10-PadB21)") (class "Default")
      (node (ref "U3") (pin "B21") (pinfunction "ANB10_B21") (pintype "passive"))
    )
    (net (code "192") (name "unconnected-(U3B-ANB11-PadA21)") (class "Default")
      (node (ref "U3") (pin "A21") (pinfunction "ANB11_A21") (pintype "passive"))
    )
    (net (code "193") (name "unconnected-(U3B-ANB12-PadC21)") (class "Default")
      (node (ref "U3") (pin "C21") (pinfunction "ANB12_C21") (pintype "passive"))
    )
    (net (code "194") (name "unconnected-(U3B-ANB13-PadD21)") (class "Default")
      (node (ref "U3") (pin "D21") (pinfunction "ANB13_D21") (pintype "passive"))
    )
    (net (code "195") (name "unconnected-(U3B-ANB14-PadA22)") (class "Default")
      (node (ref "U3") (pin "A22") (pinfunction "ANB14_A22") (pintype "passive"))
    )
    (net (code "196") (name "unconnected-(U3B-ANB15-PadB22)") (class "Default")
      (node (ref "U3") (pin "B22") (pinfunction "ANB15_B22") (pintype "passive"))
    )
    (net (code "197") (name "unconnected-(U3B-ANB16-PadC22)") (class "Default")
      (node (ref "U3") (pin "C22") (pinfunction "ANB16_C22") (pintype "passive"))
    )
    (net (code "198") (name "unconnected-(U3B-ANB17-PadA23)") (class "Default")
      (node (ref "U3") (pin "A23") (pinfunction "ANB17_A23") (pintype "passive"))
    )
    (net (code "199") (name "unconnected-(U3B-ANB18-PadB23)") (class "Default")
      (node (ref "U3") (pin "B23") (pinfunction "ANB18_B23") (pintype "passive"))
    )
    (net (code "200") (name "unconnected-(U3B-ANB19-PadC23)") (class "Default")
      (node (ref "U3") (pin "C23") (pinfunction "ANB19_C23") (pintype "passive"))
    )
    (net (code "201") (name "unconnected-(U3B-ANB20-PadD22)") (class "Default")
      (node (ref "U3") (pin "D22") (pinfunction "ANB20_D22") (pintype "passive"))
    )
    (net (code "202") (name "unconnected-(U3B-ANB21-PadA24)") (class "Default")
      (node (ref "U3") (pin "A24") (pinfunction "ANB21_A24") (pintype "passive"))
    )
    (net (code "203") (name "unconnected-(U3B-ANB22-PadB24)") (class "Default")
      (node (ref "U3") (pin "B24") (pinfunction "ANB22_B24") (pintype "passive"))
    )
    (net (code "204") (name "unconnected-(U3B-ANB23-PadA25)") (class "Default")
      (node (ref "U3") (pin "A25") (pinfunction "ANB23_A25") (pintype "passive"))
    )
    (net (code "205") (name "unconnected-(U3D-CNRXC_PCSD4_GPIO88-PadAE20)") (class "Default")
      (node (ref "U3") (pin "AE20") (pinfunction "CNRXC_PCSD4_GPIO88_AE20") (pintype "input"))
    )
    (net (code "206") (name "unconnected-(U3D-CNRXD_GPIO247-PadAC20)") (class "Default")
      (node (ref "U3") (pin "AC20") (pinfunction "CNRXD_GPIO247_AC20") (pintype "input"))
    )
    (net (code "207") (name "unconnected-(U3D-CNTXC_PCSD3_GPIO87-PadAF20)") (class "Default")
      (node (ref "U3") (pin "AF20") (pinfunction "CNTXC_PCSD3_GPIO87_AF20") (pintype "input"))
    )
    (net (code "208") (name "unconnected-(U3D-CNTXD_GPIO246-PadAD20)") (class "Default")
      (node (ref "U3") (pin "AD20") (pinfunction "CNTXD_GPIO246_AD20") (pintype "input"))
    )
    (net (code "209") (name "unconnected-(U3D-FR_A_RX_GPIO249-PadAE3)") (class "Default")
      (node (ref "U3") (pin "AE3") (pinfunction "FR_A_RX_GPIO249_AE3") (pintype "input"))
    )
    (net (code "210") (name "unconnected-(U3D-FR_A_TX_EN_GPIO250-PadAF3)") (class "Default")
      (node (ref "U3") (pin "AF3") (pinfunction "FR_A_TX_EN_GPIO250_AF3") (pintype "input"))
    )
    (net (code "211") (name "unconnected-(U3D-FR_A_TX_GPIO248-PadAD4)") (class "Default")
      (node (ref "U3") (pin "AD4") (pinfunction "FR_A_TX_GPIO248_AD4") (pintype "input"))
    )
    (net (code "212") (name "unconnected-(U3D-FR_B_RX_GPIO252-PadAE4)") (class "Default")
      (node (ref "U3") (pin "AE4") (pinfunction "FR_B_RX_GPIO252_AE4") (pintype "input"))
    )
    (net (code "213") (name "unconnected-(U3D-FR_B_TX_EN_GPIO253-PadAF4)") (class "Default")
      (node (ref "U3") (pin "AF4") (pinfunction "FR_B_TX_EN_GPIO253_AF4") (pintype "input"))
    )
    (net (code "214") (name "unconnected-(U3D-FR_B_TX_GPIO251-PadAD5)") (class "Default")
      (node (ref "U3") (pin "AD5") (pinfunction "FR_B_TX_GPIO251_AD5") (pintype "input"))
    )
    (net (code "215") (name "unconnected-(U3D-PCSA0_PCSD2_GPIO96-PadAE6)") (class "Default")
      (node (ref "U3") (pin "AE6") (pinfunction "PCSA0_PCSD2_GPIO96_AE6") (pintype "input"))
    )
    (net (code "216") (name "unconnected-(U3D-PCSA1_PCSE0_GPIO97-PadAC6)") (class "Default")
      (node (ref "U3") (pin "AC6") (pinfunction "PCSA1_PCSE0_GPIO97_AC6") (pintype "input"))
    )
    (net (code "217") (name "unconnected-(U3D-PCSA2_SOUTE_GPIO98-PadAC7)") (class "Default")
      (node (ref "U3") (pin "AC7") (pinfunction "PCSA2_SOUTE_GPIO98_AC7") (pintype "input"))
    )
    (net (code "218") (name "unconnected-(U3D-PCSA3_SINE_GPIO99-PadAE7)") (class "Default")
      (node (ref "U3") (pin "AE7") (pinfunction "PCSA3_SINE_GPIO99_AE7") (pintype "input"))
    )
    (net (code "219") (name "unconnected-(U3D-PCSA4_SCKE_GPIO100-PadAE5)") (class "Default")
      (node (ref "U3") (pin "AE5") (pinfunction "PCSA4_SCKE_GPIO100_AE5") (pintype "input"))
    )
    (net (code "220") (name "unconnected-(U3D-PCSA5_ETRIG1_GPIO101-PadAD6)") (class "Default")
      (node (ref "U3") (pin "AD6") (pinfunction "PCSA5_ETRIG1_GPIO101_AD6") (pintype "input"))
    )
    (net (code "221") (name "unconnected-(U3D-PCSB0_PCSD2_GPIO105-PadAD9)") (class "Default")
      (node (ref "U3") (pin "AD9") (pinfunction "PCSB0_PCSD2_GPIO105_AD9") (pintype "input"))
    )
    (net (code "222") (name "unconnected-(U3D-PCSB1_PCSD0_GPIO106-PadAC9)") (class "Default")
      (node (ref "U3") (pin "AC9") (pinfunction "PCSB1_PCSD0_GPIO106_AC9") (pintype "input"))
    )
    (net (code "223") (name "unconnected-(U3D-PCSB2_SOUTC_GPIO107-PadAF8)") (class "Default")
      (node (ref "U3") (pin "AF8") (pinfunction "PCSB2_SOUTC_GPIO107_AF8") (pintype "input"))
    )
    (net (code "224") (name "unconnected-(U3D-PCSB3_SINC_GPIO108-PadAD10)") (class "Default")
      (node (ref "U3") (pin "AD10") (pinfunction "PCSB3_SINC_GPIO108_AD10") (pintype "input"))
    )
    (net (code "225") (name "unconnected-(U3D-PCSB4_SCKC_GPIO109-PadAC8)") (class "Default")
      (node (ref "U3") (pin "AC8") (pinfunction "PCSB4_SCKC_GPIO109_AC8") (pintype "input"))
    )
    (net (code "226") (name "unconnected-(U3D-PCSB5_PCSC0_GPIO110-PadAF6)") (class "Default")
      (node (ref "U3") (pin "AF6") (pinfunction "PCSB5_PCSC0_GPIO110_AF6") (pintype "input"))
    )
    (net (code "227") (name "unconnected-(U3D-PCSC0_SOUT_C_LVDSM_GPIO238-PadAE21)") (class "Default")
      (node (ref "U3") (pin "AE21") (pinfunction "PCSC0_SOUT_C_LVDSM_GPIO238_AE21") (pintype "input"))
    )
    (net (code "228") (name "unconnected-(U3D-PCSC1_GPIO239-PadAC22)") (class "Default")
      (node (ref "U3") (pin "AC22") (pinfunction "PCSC1_GPIO239_AC22") (pintype "input"))
    )
    (net (code "229") (name "unconnected-(U3D-PCSC2_GPIO240-PadAE23)") (class "Default")
      (node (ref "U3") (pin "AE23") (pinfunction "PCSC2_GPIO240_AE23") (pintype "input"))
    )
    (net (code "230") (name "unconnected-(U3D-PCSC3_GPIO241-PadAD23)") (class "Default")
      (node (ref "U3") (pin "AD23") (pinfunction "PCSC3_GPIO241_AD23") (pintype "input"))
    )
    (net (code "231") (name "unconnected-(U3D-PCSC4_GPIO242-PadAF24)") (class "Default")
      (node (ref "U3") (pin "AF24") (pinfunction "PCSC4_GPIO242_AF24") (pintype "input"))
    )
    (net (code "232") (name "unconnected-(U3D-PCSC5_GPIO243-PadAE24)") (class "Default")
      (node (ref "U3") (pin "AE24") (pinfunction "PCSC5_GPIO243_AE24") (pintype "input"))
    )
    (net (code "233") (name "unconnected-(U3D-RXDB_PCSD5_GPIO92-PadN1)") (class "Default")
      (node (ref "U3") (pin "N1") (pinfunction "RXDB_PCSD5_GPIO92_N1") (pintype "input"))
    )
    (net (code "234") (name "unconnected-(U3D-RXDC_GPIO245-PadAD22)") (class "Default")
      (node (ref "U3") (pin "AD22") (pinfunction "RXDC_GPIO245_AD22") (pintype "input"))
    )
    (net (code "235") (name "unconnected-(U3D-SCKA_PCSC1_GPIO93-PadAD8)") (class "Default")
      (node (ref "U3") (pin "AD8") (pinfunction "SCKA_PCSC1_GPIO93_AD8") (pintype "input"))
    )
    (net (code "236") (name "unconnected-(U3D-SCKB_GPIO102-PadAE8)") (class "Default")
      (node (ref "U3") (pin "AE8") (pinfunction "SCKB_GPIO102_AE8") (pintype "input"))
    )
    (net (code "237") (name "unconnected-(U3D-SCKC_SCK_C_LVDSP_GPIO235-PadAD21)") (class "Default")
      (node (ref "U3") (pin "AD21") (pinfunction "SCKC_SCK_C_LVDSP_GPIO235_AD21") (pintype "input"))
    )
    (net (code "238") (name "unconnected-(U3D-SINA_PCSC2_GPIO94-PadAF7)") (class "Default")
      (node (ref "U3") (pin "AF7") (pinfunction "SINA_PCSC2_GPIO94_AF7") (pintype "input"))
    )
    (net (code "239") (name "unconnected-(U3D-SINB_GPIO103-PadAE9)") (class "Default")
      (node (ref "U3") (pin "AE9") (pinfunction "SINB_GPIO103_AE9") (pintype "input"))
    )
    (net (code "240") (name "unconnected-(U3D-SINC_SCK_C_LVDSM_GPIO236-PadAE22)") (class "Default")
      (node (ref "U3") (pin "AE22") (pinfunction "SINC_SCK_C_LVDSM_GPIO236_AE22") (pintype "input"))
    )
    (net (code "241") (name "unconnected-(U3D-SOUTA_PCSC5_GPIO95-PadAD7)") (class "Default")
      (node (ref "U3") (pin "AD7") (pinfunction "SOUTA_PCSC5_GPIO95_AD7") (pintype "input"))
    )
    (net (code "242") (name "unconnected-(U3D-SOUTB_GPIO104-PadAF9)") (class "Default")
      (node (ref "U3") (pin "AF9") (pinfunction "SOUTB_GPIO104_AF9") (pintype "input"))
    )
    (net (code "243") (name "unconnected-(U3D-SOUTC_SOUT_C_LVDSP_GPIO237-PadAF21)") (class "Default")
      (node (ref "U3") (pin "AF21") (pinfunction "SOUTC_SOUT_C_LVDSP_GPIO237_AF21") (pintype "input"))
    )
    (net (code "244") (name "unconnected-(U3D-TXDB_PCSD1_GPIO91-PadP1)") (class "Default")
      (node (ref "U3") (pin "P1") (pinfunction "TXDB_PCSD1_GPIO91_P1") (pintype "input"))
    )
    (net (code "245") (name "unconnected-(U3D-TXDC_ETRIG0_GPIO244-PadAF23)") (class "Default")
      (node (ref "U3") (pin "AF23") (pinfunction "TXDC_ETRIG0_GPIO244_AF23") (pintype "input"))
    )
  )
)
